# Connector.net
KiCad netlist of a schematic drawn in Altium Designer
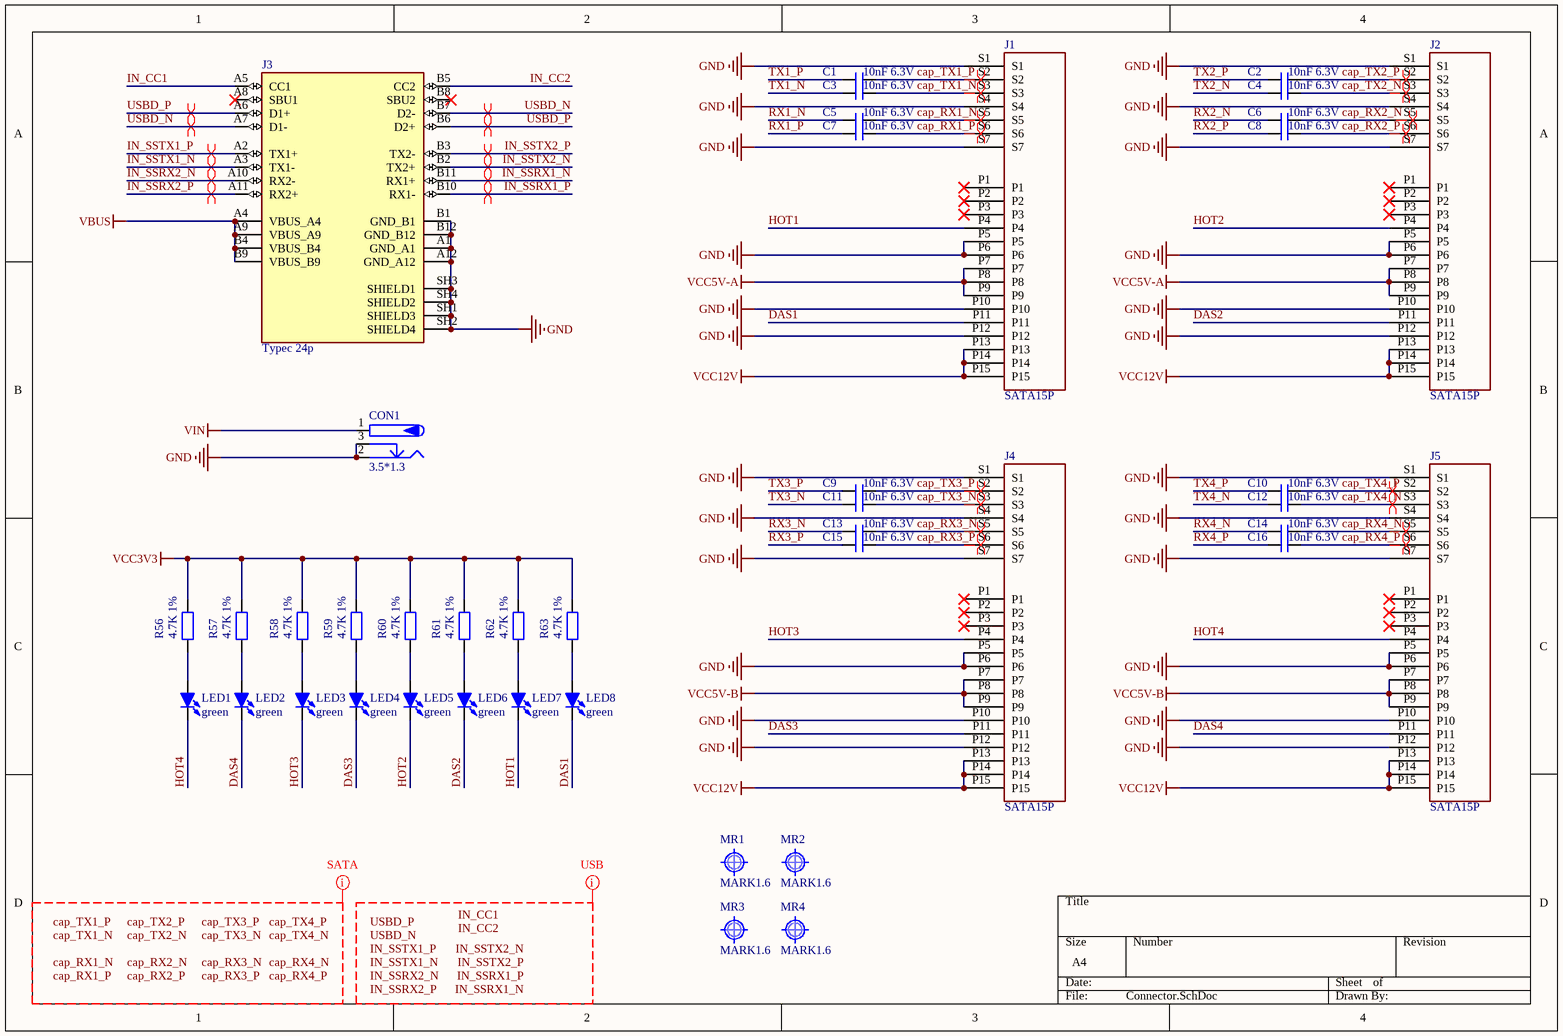
[diagram p0: Connector.SchDoc]

(export (version "E")
  (design (tool "Eeschema 10.0.6"))
  (components
    (comp (ref "C1")
      (value "10nF 6.3V")
      (footprint "C0402_L")
      (description "无极性贴片电容")
      (fields (field (name "版权归属") "源创客"))
      (libsource (lib "Capacitor") (part "C"))
    )
    (comp (ref "C2")
      (value "10nF 6.3V")
      (footprint "C0402_L")
      (description "无极性贴片电容")
      (fields (field (name "版权归属") "源创客"))
      (libsource (lib "Capacitor") (part "C"))
    )
    (comp (ref "C3")
      (value "10nF 6.3V")
      (footprint "C0402_L")
      (description "无极性贴片电容")
      (fields (field (name "版权归属") "源创客"))
      (libsource (lib "Capacitor") (part "C"))
    )
    (comp (ref "C4")
      (value "10nF 6.3V")
      (footprint "C0402_L")
      (description "无极性贴片电容")
      (fields (field (name "版权归属") "源创客"))
      (libsource (lib "Capacitor") (part "C"))
    )
    (comp (ref "C5")
      (value "10nF 6.3V")
      (footprint "C0402_L")
      (description "无极性贴片电容")
      (fields (field (name "版权归属") "源创客"))
      (libsource (lib "Capacitor") (part "C"))
    )
    (comp (ref "C6")
      (value "10nF 6.3V")
      (footprint "C0402_L")
      (description "无极性贴片电容")
      (fields (field (name "版权归属") "源创客"))
      (libsource (lib "Capacitor") (part "C"))
    )
    (comp (ref "C7")
      (value "10nF 6.3V")
      (footprint "C0402_L")
      (description "无极性贴片电容")
      (fields (field (name "版权归属") "源创客"))
      (libsource (lib "Capacitor") (part "C"))
    )
    (comp (ref "C8")
      (value "10nF 6.3V")
      (footprint "C0402_L")
      (description "无极性贴片电容")
      (fields (field (name "版权归属") "源创客"))
      (libsource (lib "Capacitor") (part "C"))
    )
    (comp (ref "C9")
      (value "10nF 6.3V")
      (footprint "C0402_L")
      (description "无极性贴片电容")
      (fields (field (name "版权归属") "源创客"))
      (libsource (lib "Capacitor") (part "C"))
    )
    (comp (ref "C10")
      (value "10nF 6.3V")
      (footprint "C0402_L")
      (description "无极性贴片电容")
      (fields (field (name "版权归属") "源创客"))
      (libsource (lib "Capacitor") (part "C"))
    )
    (comp (ref "C11")
      (value "10nF 6.3V")
      (footprint "C0402_L")
      (description "无极性贴片电容")
      (fields (field (name "版权归属") "源创客"))
      (libsource (lib "Capacitor") (part "C"))
    )
    (comp (ref "C12")
      (value "10nF 6.3V")
      (footprint "C0402_L")
      (description "无极性贴片电容")
      (fields (field (name "版权归属") "源创客"))
      (libsource (lib "Capacitor") (part "C"))
    )
    (comp (ref "C13")
      (value "10nF 6.3V")
      (footprint "C0402_L")
      (description "无极性贴片电容")
      (fields (field (name "版权归属") "源创客"))
      (libsource (lib "Capacitor") (part "C"))
    )
    (comp (ref "C14")
      (value "10nF 6.3V")
      (footprint "C0402_L")
      (description "无极性贴片电容")
      (fields (field (name "版权归属") "源创客"))
      (libsource (lib "Capacitor") (part "C"))
    )
    (comp (ref "C15")
      (value "10nF 6.3V")
      (footprint "C0402_L")
      (description "无极性贴片电容")
      (fields (field (name "版权归属") "源创客"))
      (libsource (lib "Capacitor") (part "C"))
    )
    (comp (ref "C16")
      (value "10nF 6.3V")
      (footprint "C0402_L")
      (description "无极性贴片电容")
      (fields (field (name "版权归属") "源创客"))
      (libsource (lib "Capacitor") (part "C"))
    )
    (comp (ref "CON1")
      (value "3.5*1.3")
      (footprint "DC-012")
      (description "低压电源接口")
      (fields (field (name "版权归属") "源创客"))
      (libsource (lib "Connector-PWR") (part "P-DC"))
    )
    (comp (ref "J1")
      (value "SATA15P")
      (footprint "SATA 15P 贴片")
      (libsource (lib "Connector-SATA&SAS") (part "SATA15P"))
    )
    (comp (ref "J2")
      (value "SATA15P")
      (footprint "SATA 15P 贴片")
      (libsource (lib "Connector-SATA&SAS") (part "SATA15P"))
    )
    (comp (ref "J3")
      (value "Typec 24p")
      (footprint "TypeC 24p 直立")
      (fields (field (name "MF") "Molex") (field (name "MP") "1054500101"))
      (libsource (lib "Connector-USB") (part "Typec 24p"))
    )
    (comp (ref "J4")
      (value "SATA15P")
      (footprint "SATA 15P 贴片")
      (libsource (lib "Connector-SATA&SAS") (part "SATA15P"))
    )
    (comp (ref "J5")
      (value "SATA15P")
      (footprint "SATA 15P 贴片")
      (libsource (lib "Connector-SATA&SAS") (part "SATA15P"))
    )
    (comp (ref "LED1")
      (value "green")
      (footprint "LED 0805G")
      (description "插件LED")
      (fields (field (name "版权归属") "源创客"))
      (libsource (lib "LED") (part "LED-3MM"))
    )
    (comp (ref "LED2")
      (value "green")
      (footprint "LED0805_W")
      (description "插件LED")
      (fields (field (name "版权归属") "源创客"))
      (libsource (lib "LED") (part "LED-3MM"))
    )
    (comp (ref "LED3")
      (value "green")
      (footprint "LED 0805G")
      (description "插件LED")
      (fields (field (name "版权归属") "源创客"))
      (libsource (lib "LED") (part "LED-3MM"))
    )
    (comp (ref "LED4")
      (value "green")
      (footprint "LED0805_W")
      (description "插件LED")
      (fields (field (name "版权归属") "源创客"))
      (libsource (lib "LED") (part "LED-3MM"))
    )
    (comp (ref "LED5")
      (value "green")
      (footprint "LED 0805G")
      (description "插件LED")
      (fields (field (name "版权归属") "源创客"))
      (libsource (lib "LED") (part "LED-3MM"))
    )
    (comp (ref "LED6")
      (value "green")
      (footprint "LED0805_W")
      (description "插件LED")
      (fields (field (name "版权归属") "源创客"))
      (libsource (lib "LED") (part "LED-3MM"))
    )
    (comp (ref "LED7")
      (value "green")
      (footprint "LED 0805G")
      (description "插件LED")
      (fields (field (name "版权归属") "源创客"))
      (libsource (lib "LED") (part "LED-3MM"))
    )
    (comp (ref "LED8")
      (value "green")
      (footprint "LED0805_W")
      (description "插件LED")
      (fields (field (name "版权归属") "源创客"))
      (libsource (lib "LED") (part "LED-3MM"))
    )
    (comp (ref "MR1")
      (value "MARK1.6")
      (footprint "Mark 1")
      (description "光学定位点")
      (fields (field (name "版权归属") "源创客"))
      (libsource (lib "Hole") (part "MARK"))
    )
    (comp (ref "MR2")
      (value "MARK1.6")
      (footprint "Mark 1")
      (description "光学定位点")
      (fields (field (name "版权归属") "源创客"))
      (libsource (lib "Hole") (part "MARK"))
    )
    (comp (ref "MR3")
      (value "MARK1.6")
      (footprint "Mark 1")
      (description "光学定位点")
      (fields (field (name "版权归属") "源创客"))
      (libsource (lib "Hole") (part "MARK"))
    )
    (comp (ref "MR4")
      (value "MARK1.6")
      (footprint "Mark 1")
      (description "光学定位点")
      (fields (field (name "版权归属") "源创客"))
      (libsource (lib "Hole") (part "MARK"))
    )
    (comp (ref "R56")
      (value "4.7K 1%")
      (footprint "R0402_L")
      (description "贴片电阻")
      (fields (field (name "版权归属") "源创客"))
      (libsource (lib "Resistor") (part "R"))
    )
    (comp (ref "R57")
      (value "4.7K 1%")
      (footprint "R0402_L")
      (description "贴片电阻")
      (fields (field (name "版权归属") "源创客"))
      (libsource (lib "Resistor") (part "R"))
    )
    (comp (ref "R58")
      (value "4.7K 1%")
      (footprint "R0402_L")
      (description "贴片电阻")
      (fields (field (name "版权归属") "源创客"))
      (libsource (lib "Resistor") (part "R"))
    )
    (comp (ref "R59")
      (value "4.7K 1%")
      (footprint "R0402_L")
      (description "贴片电阻")
      (fields (field (name "版权归属") "源创客"))
      (libsource (lib "Resistor") (part "R"))
    )
    (comp (ref "R60")
      (value "4.7K 1%")
      (footprint "R0402_L")
      (description "贴片电阻")
      (fields (field (name "版权归属") "源创客"))
      (libsource (lib "Resistor") (part "R"))
    )
    (comp (ref "R61")
      (value "4.7K 1%")
      (footprint "R0402_L")
      (description "贴片电阻")
      (fields (field (name "版权归属") "源创客"))
      (libsource (lib "Resistor") (part "R"))
    )
    (comp (ref "R62")
      (value "4.7K 1%")
      (footprint "R0402_L")
      (description "贴片电阻")
      (fields (field (name "版权归属") "源创客"))
      (libsource (lib "Resistor") (part "R"))
    )
    (comp (ref "R63")
      (value "4.7K 1%")
      (footprint "R0402_L")
      (description "贴片电阻")
      (fields (field (name "版权归属") "源创客"))
      (libsource (lib "Resistor") (part "R"))
    )
  )
  (nets
    (net (code "1") (name "/DAS1") (class "Default")
      (node (ref "J1") (pin "P11") (pinfunction "P11_P11") (pintype "passive"))
      (node (ref "LED8") (pin "2") (pinfunction "K_2") (pintype "passive"))
    )
    (net (code "2") (name "/DAS2") (class "Default")
      (node (ref "J2") (pin "P11") (pinfunction "P11_P11") (pintype "passive"))
      (node (ref "LED6") (pin "2") (pinfunction "K_2") (pintype "passive"))
    )
    (net (code "3") (name "/DAS3") (class "Default")
      (node (ref "J4") (pin "P11") (pinfunction "P11_P11") (pintype "passive"))
      (node (ref "LED4") (pin "2") (pinfunction "K_2") (pintype "passive"))
    )
    (net (code "4") (name "/DAS4") (class "Default")
      (node (ref "J5") (pin "P11") (pinfunction "P11_P11") (pintype "passive"))
      (node (ref "LED2") (pin "2") (pinfunction "K_2") (pintype "passive"))
    )
    (net (code "5") (name "/HOT1") (class "Default")
      (node (ref "J1") (pin "P4") (pinfunction "P4_P4") (pintype "passive"))
      (node (ref "LED7") (pin "2") (pinfunction "K_2") (pintype "passive"))
    )
    (net (code "6") (name "/HOT2") (class "Default")
      (node (ref "J2") (pin "P4") (pinfunction "P4_P4") (pintype "passive"))
      (node (ref "LED5") (pin "2") (pinfunction "K_2") (pintype "passive"))
    )
    (net (code "7") (name "/HOT3") (class "Default")
      (node (ref "J4") (pin "P4") (pinfunction "P4_P4") (pintype "passive"))
      (node (ref "LED3") (pin "2") (pinfunction "K_2") (pintype "passive"))
    )
    (net (code "8") (name "/HOT4") (class "Default")
      (node (ref "J5") (pin "P4") (pinfunction "P4_P4") (pintype "passive"))
      (node (ref "LED1") (pin "2") (pinfunction "K_2") (pintype "passive"))
    )
    (net (code "9") (name "/IN_CC1") (class "Default")
      (node (ref "J3") (pin "A5") (pinfunction "CC1_A5") (pintype "bidirectional"))
    )
    (net (code "10") (name "/IN_CC2") (class "Default")
      (node (ref "J3") (pin "B5") (pinfunction "CC2_B5") (pintype "bidirectional"))
    )
    (net (code "11") (name "/IN_SSRX1_N") (class "Default")
      (node (ref "J3") (pin "B11") (pinfunction "RX1+_B11") (pintype "bidirectional"))
    )
    (net (code "12") (name "/IN_SSRX1_P") (class "Default")
      (node (ref "J3") (pin "B10") (pinfunction "RX1-_B10") (pintype "bidirectional"))
    )
    (net (code "13") (name "/IN_SSRX2_N") (class "Default")
      (node (ref "J3") (pin "A10") (pinfunction "RX2-_A10") (pintype "bidirectional"))
    )
    (net (code "14") (name "/IN_SSRX2_P") (class "Default")
      (node (ref "J3") (pin "A11") (pinfunction "RX2+_A11") (pintype "bidirectional"))
    )
    (net (code "15") (name "/IN_SSTX1_N") (class "Default")
      (node (ref "J3") (pin "A3") (pinfunction "TX1-_A3") (pintype "bidirectional"))
    )
    (net (code "16") (name "/IN_SSTX1_P") (class "Default")
      (node (ref "J3") (pin "A2") (pinfunction "TX1+_A2") (pintype "bidirectional"))
    )
    (net (code "17") (name "/IN_SSTX2_N") (class "Default")
      (node (ref "J3") (pin "B2") (pinfunction "TX2+_B2") (pintype "bidirectional"))
    )
    (net (code "18") (name "/IN_SSTX2_P") (class "Default")
      (node (ref "J3") (pin "B3") (pinfunction "TX2-_B3") (pintype "bidirectional"))
    )
    (net (code "19") (name "/RX1_N") (class "Default")
      (node (ref "C5") (pin "2") (pinfunction "2_2") (pintype "passive"))
    )
    (net (code "20") (name "/RX1_P") (class "Default")
      (node (ref "C7") (pin "2") (pinfunction "2_2") (pintype "passive"))
    )
    (net (code "21") (name "/RX2_N") (class "Default")
      (node (ref "C6") (pin "2") (pinfunction "2_2") (pintype "passive"))
    )
    (net (code "22") (name "/RX2_P") (class "Default")
      (node (ref "C8") (pin "2") (pinfunction "2_2") (pintype "passive"))
    )
    (net (code "23") (name "/RX3_N") (class "Default")
      (node (ref "C13") (pin "2") (pinfunction "2_2") (pintype "passive"))
    )
    (net (code "24") (name "/RX3_P") (class "Default")
      (node (ref "C15") (pin "2") (pinfunction "2_2") (pintype "passive"))
    )
    (net (code "25") (name "/RX4_N") (class "Default")
      (node (ref "C14") (pin "2") (pinfunction "2_2") (pintype "passive"))
    )
    (net (code "26") (name "/RX4_P") (class "Default")
      (node (ref "C16") (pin "2") (pinfunction "2_2") (pintype "passive"))
    )
    (net (code "27") (name "/TX1_N") (class "Default")
      (node (ref "C3") (pin "2") (pinfunction "2_2") (pintype "passive"))
    )
    (net (code "28") (name "/TX1_P") (class "Default")
      (node (ref "C1") (pin "2") (pinfunction "2_2") (pintype "passive"))
    )
    (net (code "29") (name "/TX2_N") (class "Default")
      (node (ref "C4") (pin "2") (pinfunction "2_2") (pintype "passive"))
    )
    (net (code "30") (name "/TX2_P") (class "Default")
      (node (ref "C2") (pin "2") (pinfunction "2_2") (pintype "passive"))
    )
    (net (code "31") (name "/TX3_N") (class "Default")
      (node (ref "C11") (pin "2") (pinfunction "2_2") (pintype "passive"))
    )
    (net (code "32") (name "/TX3_P") (class "Default")
      (node (ref "C9") (pin "2") (pinfunction "2_2") (pintype "passive"))
    )
    (net (code "33") (name "/TX4_N") (class "Default")
      (node (ref "C12") (pin "2") (pinfunction "2_2") (pintype "passive"))
    )
    (net (code "34") (name "/TX4_P") (class "Default")
      (node (ref "C10") (pin "2") (pinfunction "2_2") (pintype "passive"))
    )
    (net (code "35") (name "/USBD_N") (class "Default")
      (node (ref "J3") (pin "A7") (pinfunction "D1-_A7") (pintype "bidirectional"))
      (node (ref "J3") (pin "B7") (pinfunction "D2-_B7") (pintype "bidirectional"))
    )
    (net (code "36") (name "/USBD_P") (class "Default")
      (node (ref "J3") (pin "A6") (pinfunction "D1+_A6") (pintype "bidirectional"))
      (node (ref "J3") (pin "B6") (pinfunction "D2+_B6") (pintype "bidirectional"))
    )
    (net (code "37") (name "/cap_RX1_N") (class "Default")
      (node (ref "C5") (pin "1") (pinfunction "1_1") (pintype "passive"))
      (node (ref "J1") (pin "S5") (pinfunction "S5_S5") (pintype "passive"))
    )
    (net (code "38") (name "/cap_RX1_P") (class "Default")
      (node (ref "C7") (pin "1") (pinfunction "1_1") (pintype "passive"))
      (node (ref "J1") (pin "S6") (pinfunction "S6_S6") (pintype "passive"))
    )
    (net (code "39") (name "/cap_RX2_N") (class "Default")
      (node (ref "C6") (pin "1") (pinfunction "1_1") (pintype "passive"))
      (node (ref "J2") (pin "S5") (pinfunction "S5_S5") (pintype "passive"))
    )
    (net (code "40") (name "/cap_RX2_P") (class "Default")
      (node (ref "C8") (pin "1") (pinfunction "1_1") (pintype "passive"))
      (node (ref "J2") (pin "S6") (pinfunction "S6_S6") (pintype "passive"))
    )
    (net (code "41") (name "/cap_RX3_N") (class "Default")
      (node (ref "C13") (pin "1") (pinfunction "1_1") (pintype "passive"))
      (node (ref "J4") (pin "S5") (pinfunction "S5_S5") (pintype "passive"))
    )
    (net (code "42") (name "/cap_RX3_P") (class "Default")
      (node (ref "C15") (pin "1") (pinfunction "1_1") (pintype "passive"))
      (node (ref "J4") (pin "S6") (pinfunction "S6_S6") (pintype "passive"))
    )
    (net (code "43") (name "/cap_RX4_N") (class "Default")
      (node (ref "C14") (pin "1") (pinfunction "1_1") (pintype "passive"))
      (node (ref "J5") (pin "S5") (pinfunction "S5_S5") (pintype "passive"))
    )
    (net (code "44") (name "/cap_RX4_P") (class "Default")
      (node (ref "C16") (pin "1") (pinfunction "1_1") (pintype "passive"))
      (node (ref "J5") (pin "S6") (pinfunction "S6_S6") (pintype "passive"))
    )
    (net (code "45") (name "/cap_TX1_N") (class "Default")
      (node (ref "C3") (pin "1") (pinfunction "1_1") (pintype "passive"))
      (node (ref "J1") (pin "S3") (pinfunction "S3_S3") (pintype "passive"))
    )
    (net (code "46") (name "/cap_TX1_P") (class "Default")
      (node (ref "C1") (pin "1") (pinfunction "1_1") (pintype "passive"))
      (node (ref "J1") (pin "S2") (pinfunction "S2_S2") (pintype "passive"))
    )
    (net (code "47") (name "/cap_TX2_N") (class "Default")
      (node (ref "C4") (pin "1") (pinfunction "1_1") (pintype "passive"))
      (node (ref "J2") (pin "S3") (pinfunction "S3_S3") (pintype "passive"))
    )
    (net (code "48") (name "/cap_TX2_P") (class "Default")
      (node (ref "C2") (pin "1") (pinfunction "1_1") (pintype "passive"))
      (node (ref "J2") (pin "S2") (pinfunction "S2_S2") (pintype "passive"))
    )
    (net (code "49") (name "/cap_TX3_N") (class "Default")
      (node (ref "C11") (pin "1") (pinfunction "1_1") (pintype "passive"))
      (node (ref "J4") (pin "S3") (pinfunction "S3_S3") (pintype "passive"))
    )
    (net (code "50") (name "/cap_TX3_P") (class "Default")
      (node (ref "C9") (pin "1") (pinfunction "1_1") (pintype "passive"))
      (node (ref "J4") (pin "S2") (pinfunction "S2_S2") (pintype "passive"))
    )
    (net (code "51") (name "/cap_TX4_N") (class "Default")
      (node (ref "C12") (pin "1") (pinfunction "1_1") (pintype "passive"))
      (node (ref "J5") (pin "S3") (pinfunction "S3_S3") (pintype "passive"))
    )
    (net (code "52") (name "/cap_TX4_P") (class "Default")
      (node (ref "C10") (pin "1") (pinfunction "1_1") (pintype "passive"))
      (node (ref "J5") (pin "S2") (pinfunction "S2_S2") (pintype "passive"))
    )
    (net (code "53") (name "GND") (class "Default")
      (node (ref "CON1") (pin "2") (pintype "power_in"))
      (node (ref "CON1") (pin "3") (pintype "power_in"))
      (node (ref "J1") (pin "P10") (pinfunction "P10_P10") (pintype "passive"))
      (node (ref "J1") (pin "P12") (pinfunction "P12_P12") (pintype "passive"))
      (node (ref "J1") (pin "P5") (pinfunction "P5_P5") (pintype "passive"))
      (node (ref "J1") (pin "P6") (pinfunction "P6_P6") (pintype "passive"))
      (node (ref "J1") (pin "S1") (pinfunction "S1_S1") (pintype "passive"))
      (node (ref "J1") (pin "S4") (pinfunction "S4_S4") (pintype "passive"))
      (node (ref "J1") (pin "S7") (pinfunction "S7_S7") (pintype "passive"))
      (node (ref "J2") (pin "P10") (pinfunction "P10_P10") (pintype "passive"))
      (node (ref "J2") (pin "P12") (pinfunction "P12_P12") (pintype "passive"))
      (node (ref "J2") (pin "P5") (pinfunction "P5_P5") (pintype "passive"))
      (node (ref "J2") (pin "P6") (pinfunction "P6_P6") (pintype "passive"))
      (node (ref "J2") (pin "S1") (pinfunction "S1_S1") (pintype "passive"))
      (node (ref "J2") (pin "S4") (pinfunction "S4_S4") (pintype "passive"))
      (node (ref "J2") (pin "S7") (pinfunction "S7_S7") (pintype "passive"))
      (node (ref "J3") (pin "A1") (pinfunction "GND_A1_A1") (pintype "power_in"))
      (node (ref "J3") (pin "A12") (pinfunction "GND_A12_A12") (pintype "power_in"))
      (node (ref "J3") (pin "B1") (pinfunction "GND_B1_B1") (pintype "power_in"))
      (node (ref "J3") (pin "B12") (pinfunction "GND_B12_B12") (pintype "power_in"))
      (node (ref "J3") (pin "SH1") (pinfunction "SHIELD3_SH1") (pintype "passive"))
      (node (ref "J3") (pin "SH2") (pinfunction "SHIELD4_SH2") (pintype "passive"))
      (node (ref "J3") (pin "SH3") (pinfunction "SHIELD1_SH3") (pintype "passive"))
      (node (ref "J3") (pin "SH4") (pinfunction "SHIELD2_SH4") (pintype "passive"))
      (node (ref "J4") (pin "P10") (pinfunction "P10_P10") (pintype "passive"))
      (node (ref "J4") (pin "P12") (pinfunction "P12_P12") (pintype "passive"))
      (node (ref "J4") (pin "P5") (pinfunction "P5_P5") (pintype "passive"))
      (node (ref "J4") (pin "P6") (pinfunction "P6_P6") (pintype "passive"))
      (node (ref "J4") (pin "S1") (pinfunction "S1_S1") (pintype "passive"))
      (node (ref "J4") (pin "S4") (pinfunction "S4_S4") (pintype "passive"))
      (node (ref "J4") (pin "S7") (pinfunction "S7_S7") (pintype "passive"))
      (node (ref "J5") (pin "P10") (pinfunction "P10_P10") (pintype "passive"))
      (node (ref "J5") (pin "P12") (pinfunction "P12_P12") (pintype "passive"))
      (node (ref "J5") (pin "P5") (pinfunction "P5_P5") (pintype "passive"))
      (node (ref "J5") (pin "P6") (pinfunction "P6_P6") (pintype "passive"))
      (node (ref "J5") (pin "S1") (pinfunction "S1_S1") (pintype "passive"))
      (node (ref "J5") (pin "S4") (pinfunction "S4_S4") (pintype "passive"))
      (node (ref "J5") (pin "S7") (pinfunction "S7_S7") (pintype "passive"))
    )
    (net (code "54") (name "Net-(LED1-A)") (class "Default")
      (node (ref "LED1") (pin "1") (pinfunction "A_1") (pintype "passive"))
      (node (ref "R56") (pin "2") (pinfunction "2_2") (pintype "passive"))
    )
    (net (code "55") (name "Net-(LED2-A)") (class "Default")
      (node (ref "LED2") (pin "1") (pinfunction "A_1") (pintype "passive"))
      (node (ref "R57") (pin "2") (pinfunction "2_2") (pintype "passive"))
    )
    (net (code "56") (name "Net-(LED3-A)") (class "Default")
      (node (ref "LED3") (pin "1") (pinfunction "A_1") (pintype "passive"))
      (node (ref "R58") (pin "2") (pinfunction "2_2") (pintype "passive"))
    )
    (net (code "57") (name "Net-(LED4-A)") (class "Default")
      (node (ref "LED4") (pin "1") (pinfunction "A_1") (pintype "passive"))
      (node (ref "R59") (pin "2") (pinfunction "2_2") (pintype "passive"))
    )
    (net (code "58") (name "Net-(LED5-A)") (class "Default")
      (node (ref "LED5") (pin "1") (pinfunction "A_1") (pintype "passive"))
      (node (ref "R60") (pin "2") (pinfunction "2_2") (pintype "passive"))
    )
    (net (code "59") (name "Net-(LED6-A)") (class "Default")
      (node (ref "LED6") (pin "1") (pinfunction "A_1") (pintype "passive"))
      (node (ref "R61") (pin "2") (pinfunction "2_2") (pintype "passive"))
    )
    (net (code "60") (name "Net-(LED7-A)") (class "Default")
      (node (ref "LED7") (pin "1") (pinfunction "A_1") (pintype "passive"))
      (node (ref "R62") (pin "2") (pinfunction "2_2") (pintype "passive"))
    )
    (net (code "61") (name "Net-(LED8-A)") (class "Default")
      (node (ref "LED8") (pin "1") (pinfunction "A_1") (pintype "passive"))
      (node (ref "R63") (pin "2") (pinfunction "2_2") (pintype "passive"))
    )
    (net (code "62") (name "VBUS") (class "Default")
      (node (ref "J3") (pin "A4") (pinfunction "VBUS_A4_A4") (pintype "power_in"))
      (node (ref "J3") (pin "A9") (pinfunction "VBUS_A9_A9") (pintype "power_in"))
      (node (ref "J3") (pin "B4") (pinfunction "VBUS_B4_B4") (pintype "power_in"))
      (node (ref "J3") (pin "B9") (pinfunction "VBUS_B9_B9") (pintype "power_in"))
    )
    (net (code "63") (name "VCC3V3") (class "Default")
      (node (ref "R56") (pin "1") (pinfunction "1_1") (pintype "passive"))
      (node (ref "R57") (pin "1") (pinfunction "1_1") (pintype "passive"))
      (node (ref "R58") (pin "1") (pinfunction "1_1") (pintype "passive"))
      (node (ref "R59") (pin "1") (pinfunction "1_1") (pintype "passive"))
      (node (ref "R60") (pin "1") (pinfunction "1_1") (pintype "passive"))
      (node (ref "R61") (pin "1") (pinfunction "1_1") (pintype "passive"))
      (node (ref "R62") (pin "1") (pinfunction "1_1") (pintype "passive"))
      (node (ref "R63") (pin "1") (pinfunction "1_1") (pintype "passive"))
    )
    (net (code "64") (name "VCC5V-A") (class "Default")
      (node (ref "J1") (pin "P7") (pinfunction "P7_P7") (pintype "passive"))
      (node (ref "J1") (pin "P8") (pinfunction "P8_P8") (pintype "passive"))
      (node (ref "J1") (pin "P9") (pinfunction "P9_P9") (pintype "passive"))
      (node (ref "J2") (pin "P7") (pinfunction "P7_P7") (pintype "passive"))
      (node (ref "J2") (pin "P8") (pinfunction "P8_P8") (pintype "passive"))
      (node (ref "J2") (pin "P9") (pinfunction "P9_P9") (pintype "passive"))
    )
    (net (code "65") (name "VCC5V-B") (class "Default")
      (node (ref "J4") (pin "P7") (pinfunction "P7_P7") (pintype "passive"))
      (node (ref "J4") (pin "P8") (pinfunction "P8_P8") (pintype "passive"))
      (node (ref "J4") (pin "P9") (pinfunction "P9_P9") (pintype "passive"))
      (node (ref "J5") (pin "P7") (pinfunction "P7_P7") (pintype "passive"))
      (node (ref "J5") (pin "P8") (pinfunction "P8_P8") (pintype "passive"))
      (node (ref "J5") (pin "P9") (pinfunction "P9_P9") (pintype "passive"))
    )
    (net (code "66") (name "VCC12V") (class "Default")
      (node (ref "J1") (pin "P13") (pinfunction "P13_P13") (pintype "passive"))
      (node (ref "J1") (pin "P14") (pinfunction "P14_P14") (pintype "passive"))
      (node (ref "J1") (pin "P15") (pinfunction "P15_P15") (pintype "passive"))
      (node (ref "J2") (pin "P13") (pinfunction "P13_P13") (pintype "passive"))
      (node (ref "J2") (pin "P14") (pinfunction "P14_P14") (pintype "passive"))
      (node (ref "J2") (pin "P15") (pinfunction "P15_P15") (pintype "passive"))
      (node (ref "J4") (pin "P13") (pinfunction "P13_P13") (pintype "passive"))
      (node (ref "J4") (pin "P14") (pinfunction "P14_P14") (pintype "passive"))
      (node (ref "J4") (pin "P15") (pinfunction "P15_P15") (pintype "passive"))
      (node (ref "J5") (pin "P13") (pinfunction "P13_P13") (pintype "passive"))
      (node (ref "J5") (pin "P14") (pinfunction "P14_P14") (pintype "passive"))
      (node (ref "J5") (pin "P15") (pinfunction "P15_P15") (pintype "passive"))
    )
    (net (code "67") (name "VIN") (class "Default") (node (ref "CON1") (pin "1") (pintype "power_in")))
    (net (code "68") (name "unconnected-(J1-PadP1)") (class "Default")
      (node (ref "J1") (pin "P1") (pinfunction "P1_P1") (pintype "passive+no_connect"))
    )
    (net (code "69") (name "unconnected-(J1-PadP2)") (class "Default")
      (node (ref "J1") (pin "P2") (pinfunction "P2_P2") (pintype "passive+no_connect"))
    )
    (net (code "70") (name "unconnected-(J1-PadP3)") (class "Default")
      (node (ref "J1") (pin "P3") (pinfunction "P3_P3") (pintype "passive+no_connect"))
    )
    (net (code "71") (name "unconnected-(J2-PadP1)") (class "Default")
      (node (ref "J2") (pin "P1") (pinfunction "P1_P1") (pintype "passive+no_connect"))
    )
    (net (code "72") (name "unconnected-(J2-PadP2)") (class "Default")
      (node (ref "J2") (pin "P2") (pinfunction "P2_P2") (pintype "passive+no_connect"))
    )
    (net (code "73") (name "unconnected-(J2-PadP3)") (class "Default")
      (node (ref "J2") (pin "P3") (pinfunction "P3_P3") (pintype "passive+no_connect"))
    )
    (net (code "74") (name "unconnected-(J3-SBU1-PadA8)") (class "Default")
      (node (ref "J3") (pin "A8") (pinfunction "SBU1_A8") (pintype "bidirectional+no_connect"))
    )
    (net (code "75") (name "unconnected-(J3-SBU2-PadB8)") (class "Default")
      (node (ref "J3") (pin "B8") (pinfunction "SBU2_B8") (pintype "bidirectional+no_connect"))
    )
    (net (code "76") (name "unconnected-(J4-PadP1)") (class "Default")
      (node (ref "J4") (pin "P1") (pinfunction "P1_P1") (pintype "passive+no_connect"))
    )
    (net (code "77") (name "unconnected-(J4-PadP2)") (class "Default")
      (node (ref "J4") (pin "P2") (pinfunction "P2_P2") (pintype "passive+no_connect"))
    )
    (net (code "78") (name "unconnected-(J4-PadP3)") (class "Default")
      (node (ref "J4") (pin "P3") (pinfunction "P3_P3") (pintype "passive+no_connect"))
    )
    (net (code "79") (name "unconnected-(J5-PadP1)") (class "Default")
      (node (ref "J5") (pin "P1") (pinfunction "P1_P1") (pintype "passive+no_connect"))
    )
    (net (code "80") (name "unconnected-(J5-PadP2)") (class "Default")
      (node (ref "J5") (pin "P2") (pinfunction "P2_P2") (pintype "passive+no_connect"))
    )
    (net (code "81") (name "unconnected-(J5-PadP3)") (class "Default")
      (node (ref "J5") (pin "P3") (pinfunction "P3_P3") (pintype "passive+no_connect"))
    )
  )
)
